# RD_BUCK.net
KiCad netlist of a schematic drawn in Altium Designer
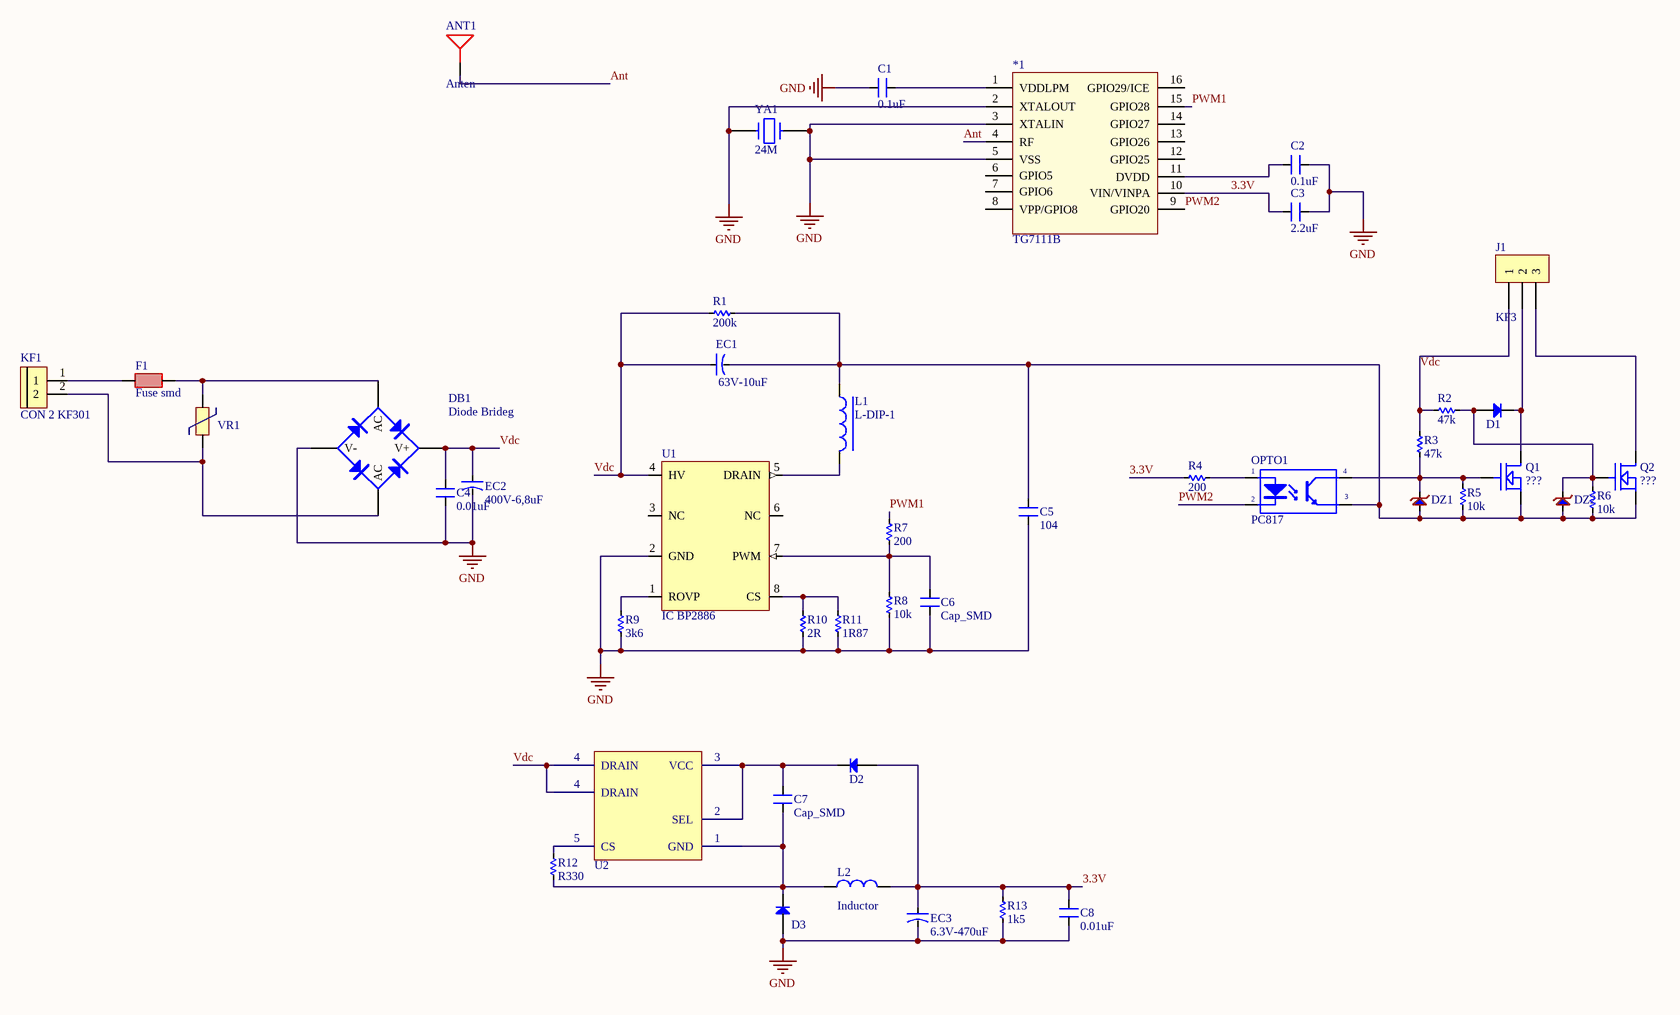
[diagram p0: RD_BUCK.SchDoc]

(export (version "E")
  (design (tool "Eeschema 10.0.6"))
  (components
    (comp (ref "*1") (value "TG7111B") (footprint "MD:SO16") (libsource (lib "MD") (part "TG7111B")))
    (comp (ref "ANT1")
      (value "Anten")
      (footprint "Module:Anten 2.4GHz 15.7-5.7 - duplicate")
      (fields
        (field (name "MANUFACTURER") "Würth Elektronik eiSos GmbH")
        (field (name "PARTNO") "613002143121")
        (field (name "CREATED BY") "Karrer Zheng")
      )
      (libsource (lib "MD") (part "Anten"))
    )
    (comp (ref "C1") (value "0.1uF") (footprint "CN-SMD-0603") (libsource (lib "MD") (part "Cap_SMD")))
    (comp (ref "C2") (value "0.1uF") (footprint "CN-SMD-0603") (libsource (lib "MD") (part "Cap_SMD")))
    (comp (ref "C3") (value "2.2uF") (footprint "CN-SMD-0603") (libsource (lib "MD") (part "Cap_SMD")))
    (comp (ref "C4") (value "0.01uF") (footprint "CN-SMD-0805") (libsource (lib "MD") (part "Cap_SMD")))
    (comp (ref "C5") (value "104") (footprint "CN-SMD-0603") (libsource (lib "MD") (part "Cap_SMD")))
    (comp (ref "C6") (value "Cap_SMD") (footprint "CN-SMD-0603") (libsource (lib "MD") (part "Cap_SMD")))
    (comp (ref "C7") (value "Cap_SMD") (footprint "CN-SMD-0805") (libsource (lib "MD") (part "Cap_SMD")))
    (comp (ref "C8") (value "0.01uF") (footprint "CN-SMD-0805") (libsource (lib "MD") (part "Cap_SMD")))
    (comp (ref "D1")
      (value "Diode SMD")
      (footprint "DIO-SMD-123")
      (description "Default Diode")
      (fields (field (name "PUBLISHER") "Altium Limited"))
      (libsource (lib "MD") (part "Diode SMD"))
    )
    (comp (ref "D2")
      (value "Diode SMD")
      (footprint "DIO-SMD-106")
      (description "Default Diode")
      (fields (field (name "PUBLISHER") "Altium Limited"))
      (libsource (lib "MD") (part "Diode SMD"))
    )
    (comp (ref "D3")
      (value "Diode SMD")
      (footprint "DIO-SMD-106")
      (description "Default Diode")
      (fields (field (name "PUBLISHER") "Altium Limited"))
      (libsource (lib "MD") (part "Diode SMD"))
    )
    (comp (ref "DB1")
      (value "Diode Brideg")
      (footprint "MD_ABS16_smd")
      (description "Convert AC to DC voltage, 4 pin")
      (libsource (lib "MD") (part "DIODE BRIGDE"))
    )
    (comp (ref "DZ1")
      (value "DIODE Zener")
      (footprint "MD:DIO-SMD-123")
      (description "Zenner")
      (libsource (lib "MD") (part "DIODE Zener"))
    )
    (comp (ref "DZ2")
      (value "DIODE Zener")
      (footprint "MD:DIO-SMD-123")
      (description "Zenner")
      (libsource (lib "MD") (part "DIODE Zener"))
    )
    (comp (ref "EC1")
      (value "63V-10uF")
      (footprint "CAP-ALU-SMD-C")
      (description "Polarized Capacitor (Axial)")
      (fields (field (name "PUBLISHER") "Altium Limited"))
      (libsource (lib "MD") (part "Cap_SMD_AL"))
    )
    (comp (ref "EC2")
      (value "400V-6,8uF")
      (footprint "CAP-ALU-SMD-F")
      (description "Polarized Capacitor (Axial)")
      (fields (field (name "PUBLISHER") "Altium Limited"))
      (libsource (lib "MD") (part "Cap_SMD_AL"))
    )
    (comp (ref "EC3")
      (value "6.3V-470uF")
      (footprint "CAP-ALU-SMD-F")
      (description "Polarized Capacitor (Axial)")
      (fields (field (name "PUBLISHER") "Altium Limited"))
      (libsource (lib "MD") (part "Cap_SMD_AL"))
    )
    (comp (ref "F1") (value "Fuse smd") (footprint "Fuse_smd") (libsource (lib "APESLAB") (part "Fuse_smd")))
    (comp (ref "J1")
      (value "KF3")
      (footprint "KF3-5.08")
      (fields
        (field (name "MANUFACTURER") "Würth Elektronik eiSos GmbH")
        (field (name "PARTNO") "691103110003")
        (field (name "CREATED BY") "Karrer Zheng")
      )
      (libsource (lib "MD") (part "KF3"))
    )
    (comp (ref "KF1")
      (value "CON 2 KF301")
      (footprint "Con 2 KF301 5.08")
      (description "Cắm")
      (libsource (lib "TrungVan_Lib") (part "CON 2 KF301"))
    )
    (comp (ref "L1")
      (value "L-DIP-1")
      (footprint "CUonChan:PCBComponent_1")
      (description "Inductor")
      (libsource (lib "MD") (part "L-DIP-1"))
    )
    (comp (ref "L2")
      (value "Inductor")
      (footprint "Herry:L-SMD-M-7.3x4.5")
      (libsource (lib "APESLAB") (part "Inductor"))
    )
    (comp (ref "OPTO1") (value "PC817") (footprint "PC817 smd") (libsource (lib "APESLAB") (part "PC817")))
    (comp (ref "Q1") (value "???") (footprint "SOT23-132") (libsource (lib "MD") (part "MOSFET N")))
    (comp (ref "Q2") (value "???") (footprint "SOT23-132") (libsource (lib "MD") (part "MOSFET N")))
    (comp (ref "R1")
      (value "200k")
      (footprint "RES-SMD-0603")
      (description "Resistor")
      (fields
        (field (name "MANUFACTURER") "Generic Components")
        (field (name "PUBLISHER") "Altium Hobart Technology Centre")
      )
      (libsource (lib "MD") (part "Res-SMD"))
    )
    (comp (ref "R2")
      (value "47k")
      (footprint "RES-SMD-0805")
      (description "Resistor")
      (fields
        (field (name "MANUFACTURER") "Generic Components")
        (field (name "PUBLISHER") "Altium Hobart Technology Centre")
      )
      (libsource (lib "MD") (part "Res-SMD"))
    )
    (comp (ref "R3")
      (value "47k")
      (footprint "RES-SMD-0805")
      (description "Resistor")
      (fields
        (field (name "MANUFACTURER") "Generic Components")
        (field (name "PUBLISHER") "Altium Hobart Technology Centre")
      )
      (libsource (lib "MD") (part "Res-SMD"))
    )
    (comp (ref "R4")
      (value "200")
      (footprint "RES-SMD-0603")
      (description "Resistor")
      (fields
        (field (name "MANUFACTURER") "Generic Components")
        (field (name "PUBLISHER") "Altium Hobart Technology Centre")
      )
      (libsource (lib "MD") (part "Res-SMD"))
    )
    (comp (ref "R5")
      (value "10k")
      (footprint "RES-SMD-0805")
      (description "Resistor")
      (fields
        (field (name "MANUFACTURER") "Generic Components")
        (field (name "PUBLISHER") "Altium Hobart Technology Centre")
      )
      (libsource (lib "MD") (part "Res-SMD"))
    )
    (comp (ref "R6")
      (value "10k")
      (footprint "RES-SMD-0805")
      (description "Resistor")
      (fields
        (field (name "MANUFACTURER") "Generic Components")
        (field (name "PUBLISHER") "Altium Hobart Technology Centre")
      )
      (libsource (lib "MD") (part "Res-SMD"))
    )
    (comp (ref "R7")
      (value "200")
      (footprint "RES-SMD-0603")
      (description "Resistor")
      (fields
        (field (name "MANUFACTURER") "Generic Components")
        (field (name "PUBLISHER") "Altium Hobart Technology Centre")
      )
      (libsource (lib "MD") (part "Res-SMD"))
    )
    (comp (ref "R8")
      (value "10k")
      (footprint "RES-SMD-0603")
      (description "Resistor")
      (fields
        (field (name "MANUFACTURER") "Generic Components")
        (field (name "PUBLISHER") "Altium Hobart Technology Centre")
      )
      (libsource (lib "MD") (part "Res-SMD"))
    )
    (comp (ref "R9")
      (value "3k6")
      (footprint "RES-SMD-0603")
      (description "Resistor")
      (fields
        (field (name "MANUFACTURER") "Generic Components")
        (field (name "PUBLISHER") "Altium Hobart Technology Centre")
      )
      (libsource (lib "MD") (part "Res-SMD"))
    )
    (comp (ref "R10")
      (value "2R")
      (footprint "RES-SMD-0603")
      (description "Resistor")
      (fields
        (field (name "MANUFACTURER") "Generic Components")
        (field (name "PUBLISHER") "Altium Hobart Technology Centre")
      )
      (libsource (lib "MD") (part "Res-SMD"))
    )
    (comp (ref "R11")
      (value "1R87")
      (footprint "RES-SMD-0603")
      (description "Resistor")
      (fields
        (field (name "MANUFACTURER") "Generic Components")
        (field (name "PUBLISHER") "Altium Hobart Technology Centre")
      )
      (libsource (lib "MD") (part "Res-SMD"))
    )
    (comp (ref "R12")
      (value "R330")
      (footprint "RES-SMD-0805")
      (description "Resistor")
      (fields
        (field (name "MANUFACTURER") "Generic Components")
        (field (name "PUBLISHER") "Altium Hobart Technology Centre")
      )
      (libsource (lib "MD") (part "Res-SMD"))
    )
    (comp (ref "R13")
      (value "1k5")
      (footprint "RES-SMD-0603")
      (description "Resistor")
      (fields
        (field (name "MANUFACTURER") "Generic Components")
        (field (name "PUBLISHER") "Altium Hobart Technology Centre")
      )
      (libsource (lib "MD") (part "Res-SMD"))
    )
    (comp (ref "U1")
      (value "IC BP2886")
      (footprint "MD:SO8")
      (description "Dimmable Non-isolated LFC Buck LED Driver")
      (libsource (lib "MD") (part "IC BP2886X"))
    )
    (comp (ref "U2") (value "3.3V - 5V") (footprint "BP SOT33-5L") (libsource (lib "MD") (part "IC BP2525X")))
    (comp (ref "VR1") (value "varistor") (footprint "CN2") (libsource (lib "APESLAB") (part "varistor")))
    (comp (ref "YA1")
      (value "24M")
      (footprint "XTAL-SMD")
      (description "Crystal")
      (libsource (lib "MD") (part "CRYSTAL"))
    )
  )
  (nets
    (net (code "1") (name "/3.3V") (class "Default")
      (node (ref "*1") (pin "10") (pinfunction "VIN/VINPA_10") (pintype "passive"))
      (node (ref "C3") (pin "1") (pinfunction "1_1") (pintype "passive"))
      (node (ref "C8") (pin "2") (pinfunction "2_2") (pintype "passive"))
      (node (ref "D2") (pin "1") (pinfunction "A_1") (pintype "passive"))
      (node (ref "EC3") (pin "1") (pinfunction "1_1") (pintype "passive"))
      (node (ref "L2") (pin "2") (pinfunction "2_2") (pintype "passive"))
      (node (ref "R13") (pin "2") (pinfunction "2_2") (pintype "passive"))
      (node (ref "R4") (pin "1") (pinfunction "1_1") (pintype "passive"))
    )
    (net (code "2") (name "/Ant") (class "Default")
      (node (ref "*1") (pin "4") (pinfunction "RF_4") (pintype "passive"))
      (node (ref "ANT1") (pin "1") (pinfunction "1_1") (pintype "passive"))
    )
    (net (code "3") (name "/PWM1") (class "Default")
      (node (ref "*1") (pin "15") (pinfunction "GPIO28_15") (pintype "passive"))
      (node (ref "R7") (pin "2") (pinfunction "2_2") (pintype "passive"))
    )
    (net (code "4") (name "/PWM2") (class "Default")
      (node (ref "*1") (pin "9") (pinfunction "GPIO20_9") (pintype "passive"))
      (node (ref "OPTO1") (pin "2") (pinfunction "K_2") (pintype "passive"))
    )
    (net (code "5") (name "/Vdc") (class "Default")
      (node (ref "C4") (pin "2") (pinfunction "2_2") (pintype "passive"))
      (node (ref "DB1") (pin "1") (pinfunction "V+_1") (pintype "passive"))
      (node (ref "EC1") (pin "1") (pinfunction "1_1") (pintype "passive"))
      (node (ref "EC2") (pin "1") (pinfunction "1_1") (pintype "passive"))
      (node (ref "J1") (pin "1") (pinfunction "1_1") (pintype "passive"))
      (node (ref "R1") (pin "1") (pinfunction "1_1") (pintype "passive"))
      (node (ref "R2") (pin "1") (pinfunction "1_1") (pintype "passive"))
      (node (ref "R3") (pin "1") (pinfunction "1_1") (pintype "passive"))
      (node (ref "U1") (pin "4") (pinfunction "HV_4") (pintype "passive"))
      (node (ref "U2") (pin "4") (pinfunction "DRAIN_4") (pintype "power_in"))
    )
    (net (code "6") (name "GND") (class "Default")
      (node (ref "*1") (pin "2") (pinfunction "XTALOUT_2") (pintype "passive"))
      (node (ref "*1") (pin "3") (pinfunction "XTALIN_3") (pintype "passive"))
      (node (ref "*1") (pin "5") (pinfunction "VSS_5") (pintype "passive"))
      (node (ref "C1") (pin "1") (pinfunction "1_1") (pintype "passive"))
      (node (ref "C2") (pin "2") (pinfunction "2_2") (pintype "passive"))
      (node (ref "C3") (pin "2") (pinfunction "2_2") (pintype "passive"))
      (node (ref "C4") (pin "1") (pinfunction "1_1") (pintype "passive"))
      (node (ref "C5") (pin "1") (pinfunction "1_1") (pintype "passive"))
      (node (ref "C6") (pin "1") (pinfunction "1_1") (pintype "passive"))
      (node (ref "C8") (pin "1") (pinfunction "1_1") (pintype "passive"))
      (node (ref "D3") (pin "1") (pinfunction "A_1") (pintype "passive"))
      (node (ref "DB1") (pin "4") (pinfunction "V-_4") (pintype "passive"))
      (node (ref "EC2") (pin "2") (pinfunction "2_2") (pintype "passive"))
      (node (ref "EC3") (pin "2") (pinfunction "2_2") (pintype "passive"))
      (node (ref "R10") (pin "2") (pinfunction "2_2") (pintype "passive"))
      (node (ref "R11") (pin "2") (pinfunction "2_2") (pintype "passive"))
      (node (ref "R13") (pin "1") (pinfunction "1_1") (pintype "passive"))
      (node (ref "R8") (pin "2") (pinfunction "2_2") (pintype "passive"))
      (node (ref "R9") (pin "2") (pinfunction "2_2") (pintype "passive"))
      (node (ref "U1") (pin "2") (pinfunction "GND_2") (pintype "power_in"))
      (node (ref "YA1") (pin "1") (pinfunction "1_1") (pintype "passive"))
      (node (ref "YA1") (pin "2") (pinfunction "2_2") (pintype "passive"))
    )
    (net (code "7") (name "Net-(*1-DVDD)") (class "Default")
      (node (ref "*1") (pin "11") (pinfunction "DVDD_11") (pintype "passive"))
      (node (ref "C2") (pin "1") (pinfunction "1_1") (pintype "passive"))
    )
    (net (code "8") (name "Net-(*1-VDDLPM)") (class "Default")
      (node (ref "*1") (pin "1") (pinfunction "VDDLPM_1") (pintype "passive"))
      (node (ref "C1") (pin "2") (pinfunction "2_2") (pintype "passive"))
    )
    (net (code "9") (name "Net-(D1-A)") (class "Default")
      (node (ref "D1") (pin "1") (pinfunction "A_1") (pintype "passive"))
      (node (ref "DZ2") (pin "2") (pinfunction "K_2") (pintype "passive"))
      (node (ref "Q2") (pin "1") (pinfunction "G_1") (pintype "passive"))
      (node (ref "R2") (pin "2") (pinfunction "2_2") (pintype "passive"))
      (node (ref "R6") (pin "1") (pinfunction "1_1") (pintype "passive"))
    )
    (net (code "10") (name "Net-(D1-K)") (class "Default")
      (node (ref "D1") (pin "2") (pinfunction "K_2") (pintype "passive"))
      (node (ref "J1") (pin "2") (pinfunction "2_2") (pintype "passive"))
      (node (ref "Q1") (pin "2") (pinfunction "D_2") (pintype "passive"))
    )
    (net (code "11") (name "Net-(D2-K)") (class "Default")
      (node (ref "C7") (pin "2") (pinfunction "2_2") (pintype "passive"))
      (node (ref "D2") (pin "2") (pinfunction "K_2") (pintype "passive"))
      (node (ref "U2") (pin "2") (pinfunction "SEL_2") (pintype "power_in"))
      (node (ref "U2") (pin "3") (pinfunction "VCC_3") (pintype "power_in"))
    )
    (net (code "12") (name "Net-(D3-K)") (class "Default")
      (node (ref "C7") (pin "1") (pinfunction "1_1") (pintype "passive"))
      (node (ref "D3") (pin "2") (pinfunction "K_2") (pintype "passive"))
      (node (ref "L2") (pin "1") (pinfunction "1_1") (pintype "passive"))
      (node (ref "R12") (pin "2") (pinfunction "2_2") (pintype "passive"))
      (node (ref "U2") (pin "1") (pinfunction "GND_1") (pintype "power_in"))
    )
    (net (code "13") (name "Net-(DB1-AC-Pad2)") (class "Default")
      (node (ref "DB1") (pin "2") (pinfunction "AC_2") (pintype "passive"))
      (node (ref "F1") (pin "2") (pinfunction "2_2") (pintype "passive"))
      (node (ref "VR1") (pin "2") (pintype "passive"))
    )
    (net (code "14") (name "Net-(DB1-AC-Pad3)") (class "Default")
      (node (ref "DB1") (pin "3") (pinfunction "AC_3") (pintype "passive"))
      (node (ref "KF1") (pin "2") (pinfunction "2_2") (pintype "passive"))
      (node (ref "VR1") (pin "1") (pintype "passive"))
    )
    (net (code "15") (name "Net-(DZ1-A)") (class "Default")
      (node (ref "C5") (pin "2") (pinfunction "2_2") (pintype "passive"))
      (node (ref "DZ1") (pin "1") (pinfunction "A_1") (pintype "passive"))
      (node (ref "DZ2") (pin "1") (pinfunction "A_1") (pintype "passive"))
      (node (ref "EC1") (pin "2") (pinfunction "2_2") (pintype "passive"))
      (node (ref "L1") (pin "1") (pinfunction "1_1") (pintype "passive"))
      (node (ref "OPTO1") (pin "3") (pinfunction "E_3") (pintype "passive"))
      (node (ref "Q1") (pin "3") (pinfunction "S_3") (pintype "passive"))
      (node (ref "Q2") (pin "3") (pinfunction "S_3") (pintype "passive"))
      (node (ref "R1") (pin "2") (pinfunction "2_2") (pintype "passive"))
      (node (ref "R5") (pin "2") (pinfunction "2_2") (pintype "passive"))
      (node (ref "R6") (pin "2") (pinfunction "2_2") (pintype "passive"))
    )
    (net (code "16") (name "Net-(DZ1-K)") (class "Default")
      (node (ref "DZ1") (pin "2") (pinfunction "K_2") (pintype "passive"))
      (node (ref "OPTO1") (pin "4") (pinfunction "C_4") (pintype "passive"))
      (node (ref "Q1") (pin "1") (pinfunction "G_1") (pintype "passive"))
      (node (ref "R3") (pin "2") (pinfunction "2_2") (pintype "passive"))
      (node (ref "R5") (pin "1") (pinfunction "1_1") (pintype "passive"))
    )
    (net (code "17") (name "Net-(F1-Pad1)") (class "Default")
      (node (ref "F1") (pin "1") (pinfunction "1_1") (pintype "passive"))
      (node (ref "KF1") (pin "1") (pinfunction "1_1") (pintype "passive"))
    )
    (net (code "18") (name "Net-(OPTO1-A)") (class "Default")
      (node (ref "OPTO1") (pin "1") (pinfunction "A_1") (pintype "passive"))
      (node (ref "R4") (pin "2") (pinfunction "2_2") (pintype "passive"))
    )
    (net (code "19") (name "Net-(Q2-D)") (class "Default")
      (node (ref "J1") (pin "3") (pinfunction "3_3") (pintype "passive"))
      (node (ref "Q2") (pin "2") (pinfunction "D_2") (pintype "passive"))
    )
    (net (code "20") (name "Net-(U1-CS)") (class "Default")
      (node (ref "R10") (pin "1") (pinfunction "1_1") (pintype "passive"))
      (node (ref "R11") (pin "1") (pinfunction "1_1") (pintype "passive"))
      (node (ref "U1") (pin "8") (pinfunction "CS_8") (pintype "passive"))
    )
    (net (code "21") (name "Net-(U1-DRAIN)") (class "Default")
      (node (ref "L1") (pin "2") (pinfunction "2_2") (pintype "passive"))
      (node (ref "U1") (pin "5") (pinfunction "DRAIN_5") (pintype "output"))
    )
    (net (code "22") (name "Net-(U1-PWM)") (class "Default")
      (node (ref "C6") (pin "2") (pinfunction "2_2") (pintype "passive"))
      (node (ref "R7") (pin "1") (pinfunction "1_1") (pintype "passive"))
      (node (ref "R8") (pin "1") (pinfunction "1_1") (pintype "passive"))
      (node (ref "U1") (pin "7") (pinfunction "PWM_7") (pintype "input"))
    )
    (net (code "23") (name "Net-(U1-ROVP)") (class "Default")
      (node (ref "R9") (pin "1") (pinfunction "1_1") (pintype "passive"))
      (node (ref "U1") (pin "1") (pinfunction "ROVP_1") (pintype "passive"))
    )
    (net (code "24") (name "Net-(U2-CS)") (class "Default")
      (node (ref "R12") (pin "1") (pinfunction "1_1") (pintype "passive"))
      (node (ref "U2") (pin "5") (pinfunction "CS_5") (pintype "power_in"))
    )
    (net (code "25") (name "unconnected-(*1-GPIO5-Pad6)") (class "Default")
      (node (ref "*1") (pin "6") (pinfunction "GPIO5_6") (pintype "passive"))
    )
    (net (code "26") (name "unconnected-(*1-GPIO6-Pad7)") (class "Default")
      (node (ref "*1") (pin "7") (pinfunction "GPIO6_7") (pintype "passive"))
    )
    (net (code "27") (name "unconnected-(*1-GPIO25-Pad12)") (class "Default")
      (node (ref "*1") (pin "12") (pinfunction "GPIO25_12") (pintype "passive"))
    )
    (net (code "28") (name "unconnected-(*1-GPIO26-Pad13)") (class "Default")
      (node (ref "*1") (pin "13") (pinfunction "GPIO26_13") (pintype "passive"))
    )
    (net (code "29") (name "unconnected-(*1-GPIO27-Pad14)") (class "Default")
      (node (ref "*1") (pin "14") (pinfunction "GPIO27_14") (pintype "passive"))
    )
    (net (code "30") (name "unconnected-(*1-GPIO29{slash}ICE-Pad16)") (class "Default")
      (node (ref "*1") (pin "16") (pinfunction "GPIO29/ICE_16") (pintype "passive"))
    )
    (net (code "31") (name "unconnected-(*1-VPP{slash}GPIO8-Pad8)") (class "Default")
      (node (ref "*1") (pin "8") (pinfunction "VPP/GPIO8_8") (pintype "passive"))
    )
    (net (code "32") (name "unconnected-(U1-NC-Pad3)") (class "Default")
      (node (ref "U1") (pin "3") (pinfunction "NC_3") (pintype "passive"))
    )
    (net (code "33") (name "unconnected-(U1-NC-Pad6)") (class "Default")
      (node (ref "U1") (pin "6") (pinfunction "NC_6") (pintype "passive"))
    )
  )
)
